# Sheet1.net
KiCad netlist of a schematic drawn in Altium Designer
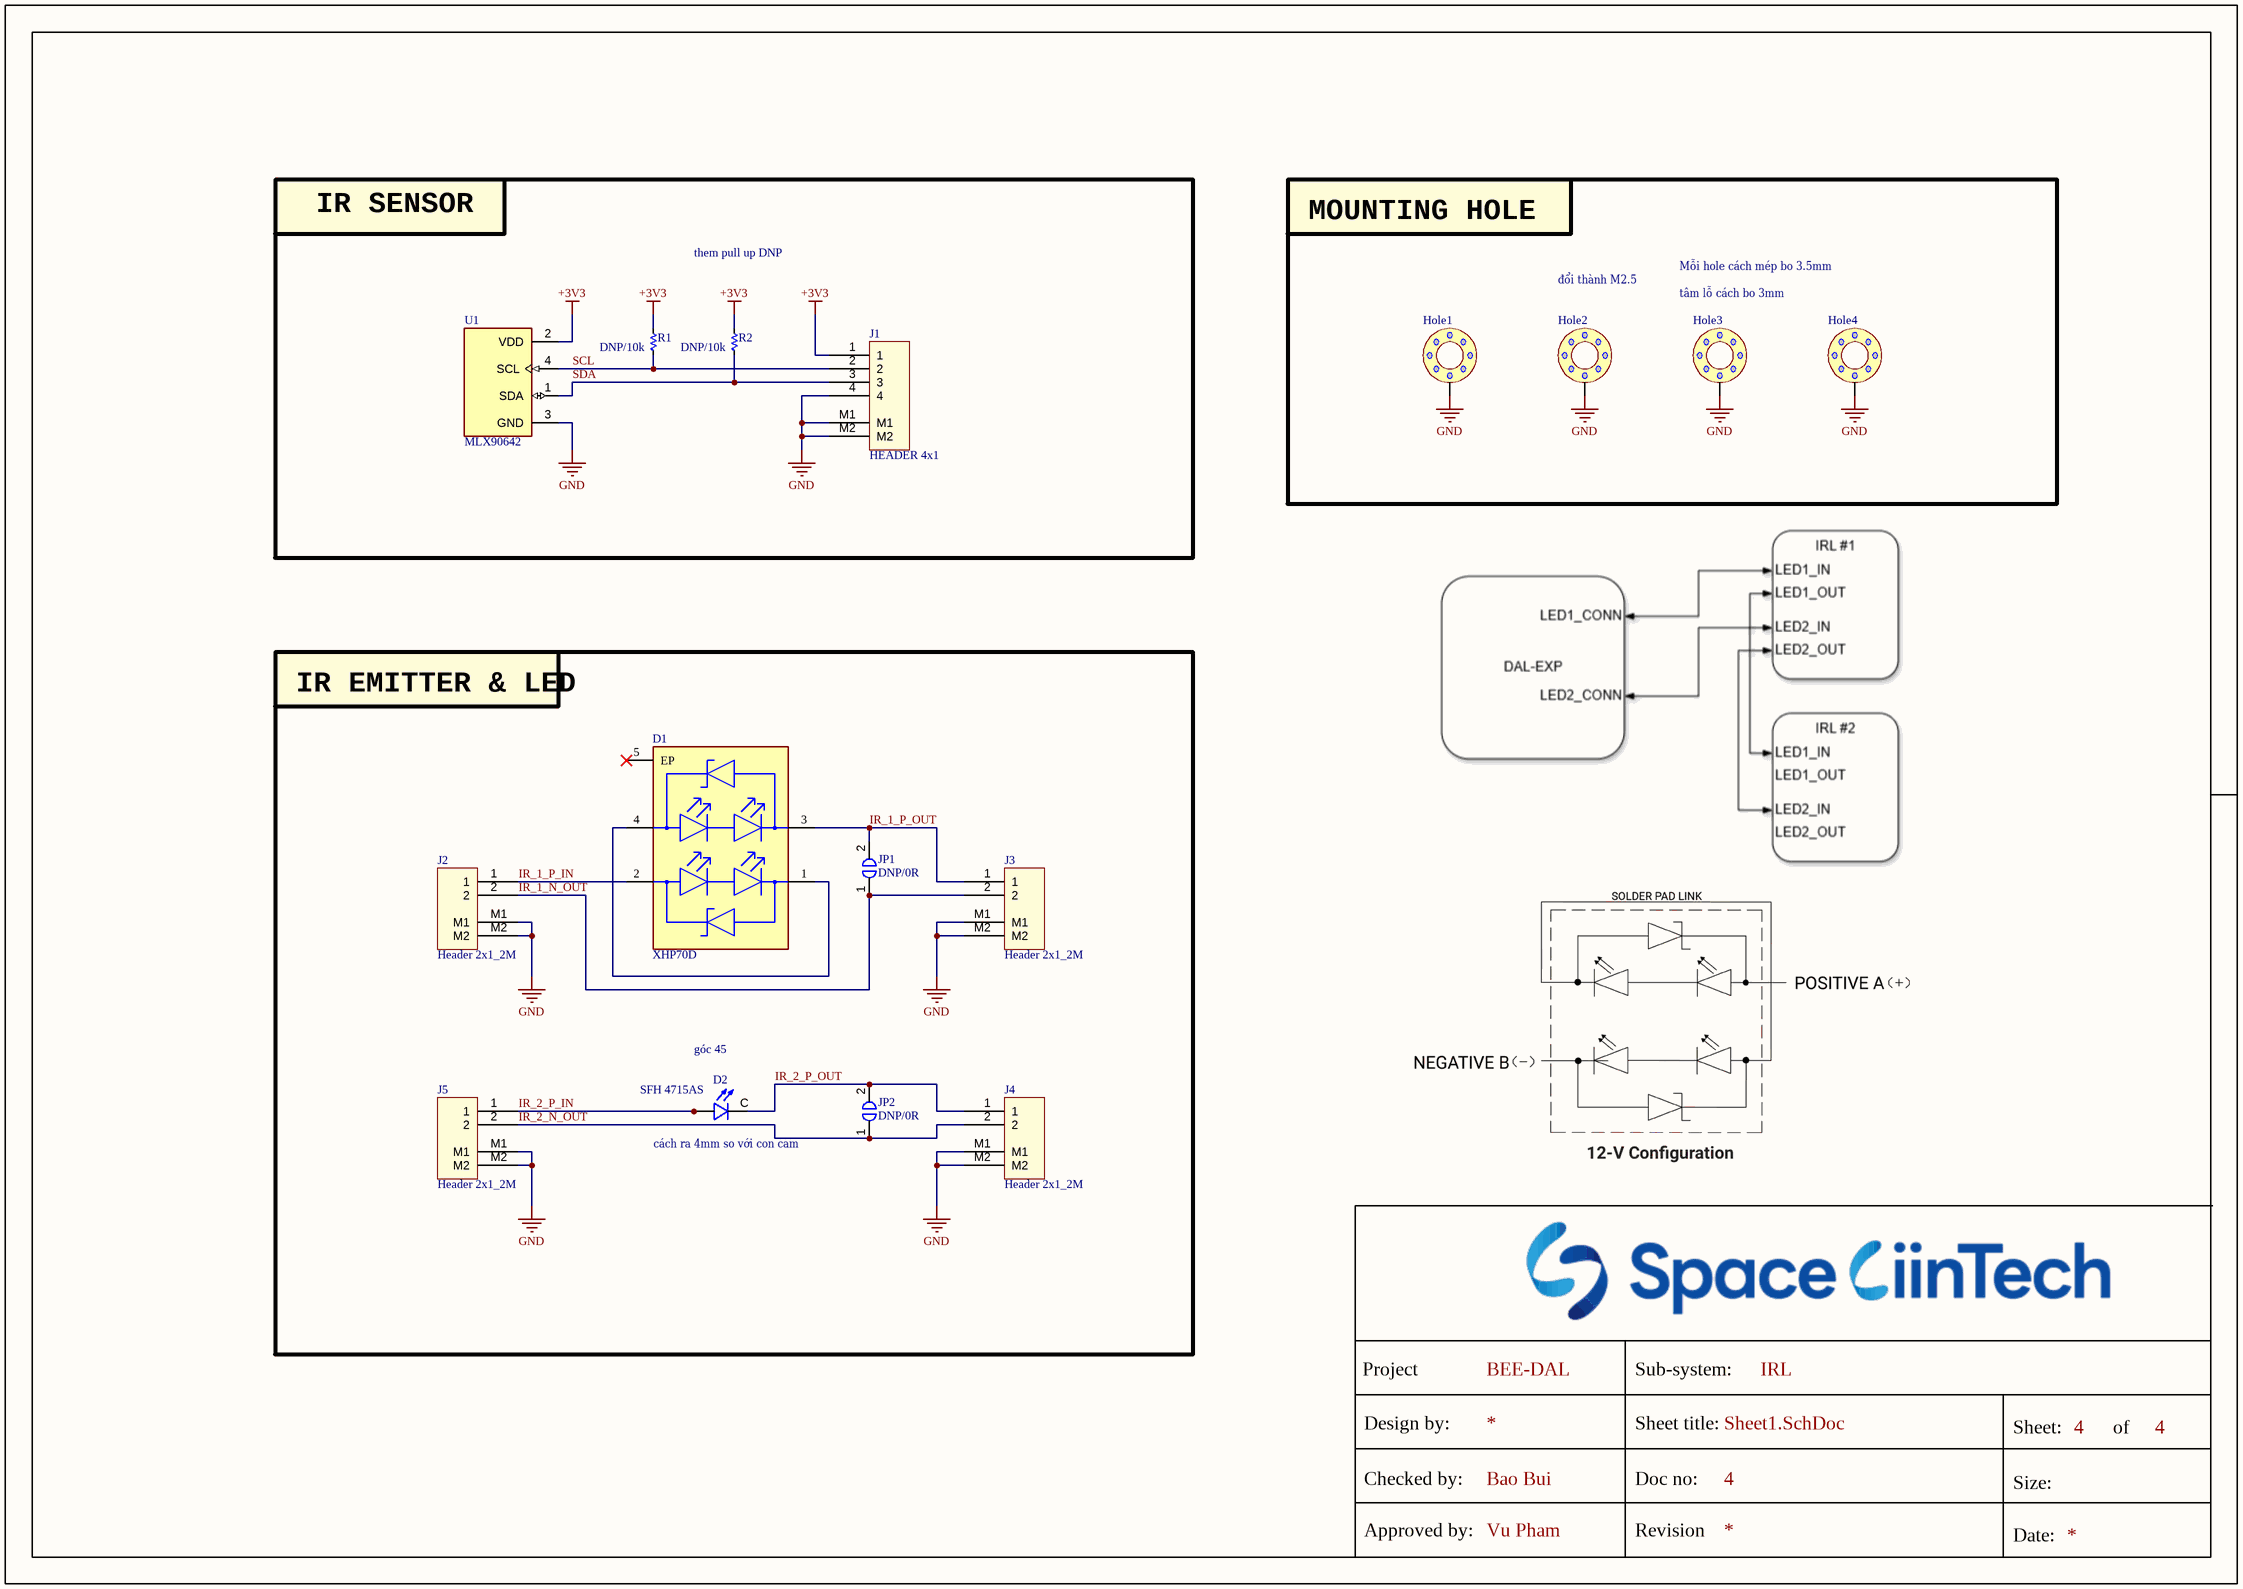
[diagram p0: Sheet1.SchDoc]

(export (version "E")
  (design (tool "Eeschema 10.0.6"))
  (components
    (comp (ref "D1")
      (value "XHP70D")
      (footprint "XHP70.3 High Intensity")
      (description "LED Lighting XLamp® XHP70.3 White, Cool 5000K 11.2V 1.05A 120° 2828")
      (libsource (lib "BEE_DAL_IRL") (part "XHP70D"))
    )
    (comp (ref "D2")
      (value "SFH 4715AS")
      (footprint "SFH 4715AS")
      (description "Infrared (IR) Emitter 860nm 3.2V 1.5A")
      (libsource (lib "BEE_DAL_IRL") (part "SFH 4715AS"))
    )
    (comp (ref "Hole1")
      (value "hole_space")
      (footprint "HEX-M3_NoVia")
      (libsource (lib "IFBschelib") (part "hole_space"))
    )
    (comp (ref "Hole2")
      (value "hole_space")
      (footprint "HEX-M3_NoVia")
      (libsource (lib "IFBschelib") (part "hole_space"))
    )
    (comp (ref "Hole3")
      (value "hole_space")
      (footprint "HEX-M3_NoVia")
      (libsource (lib "IFBschelib") (part "hole_space"))
    )
    (comp (ref "Hole4")
      (value "hole_space")
      (footprint "HEX-M3_NoVia")
      (libsource (lib "IFBschelib") (part "hole_space"))
    )
    (comp (ref "J1")
      (value "HEADER 4x1")
      (footprint "MOLEX_0532610471")
      (libsource (lib "LABLIB") (part "Header 4x1_2M"))
    )
    (comp (ref "J2")
      (value "Header 2x1_2M")
      (footprint "MOLEX_0532610271")
      (libsource (lib "") (part "Header 2x1_2M_1"))
    )
    (comp (ref "J3")
      (value "Header 2x1_2M")
      (footprint "MOLEX_0532610271")
      (libsource (lib "LABLIB") (part "Header 2x1_2M"))
    )
    (comp (ref "J4")
      (value "Header 2x1_2M")
      (footprint "MOLEX_0532610271")
      (libsource (lib "LABLIB") (part "Header 2x1_2M"))
    )
    (comp (ref "J5")
      (value "Header 2x1_2M")
      (footprint "MOLEX_0532610271")
      (libsource (lib "") (part "Header 2x1_2M_1"))
    )
    (comp (ref "JP1")
      (value "DNP/0R")
      (footprint "JUMPER_1608")
      (libsource (lib "LABLIB") (part "JUMPER_1_1"))
    )
    (comp (ref "JP2")
      (value "DNP/0R")
      (footprint "JUMPER_1608")
      (libsource (lib "LABLIB") (part "JUMPER_1_1"))
    )
    (comp (ref "R1")
      (value "DNP/10k")
      (footprint "RES_C_1608X60")
      (description "RES")
      (libsource (lib "IFBschelib") (part "_RES_B_2"))
    )
    (comp (ref "R2")
      (value "DNP/10k")
      (footprint "RES_C_1608X60")
      (description "RES")
      (libsource (lib "IFBschelib") (part "_RES_B_2"))
    )
    (comp (ref "U1")
      (value "MLX90642")
      (footprint "TO39 package")
      (description "32X24 THERMAL ARRAY, 110DEG FOV")
      (libsource (lib "BEE_DAL_IRL") (part "MLX90642"))
    )
  )
  (nets
    (net (code "1") (name "+3V3") (class "Default")
      (node (ref "J1") (pin "1") (pinfunction "1_1") (pintype "passive"))
      (node (ref "R1") (pin "1") (pinfunction "1_1") (pintype "passive"))
      (node (ref "R2") (pin "1") (pinfunction "1_1") (pintype "passive"))
      (node (ref "U1") (pin "2") (pinfunction "VDD_2") (pintype "power_in"))
    )
    (net (code "2") (name "/IR_1_N_OUT") (class "Default")
      (node (ref "J2") (pin "2") (pinfunction "2_2") (pintype "passive"))
      (node (ref "J3") (pin "2") (pinfunction "2_2") (pintype "passive"))
      (node (ref "JP1") (pin "1") (pinfunction "1_1") (pintype "passive"))
    )
    (net (code "3") (name "/IR_1_P_IN") (class "Default")
      (node (ref "D1") (pin "2") (pinfunction "1_ANODE_2") (pintype "passive"))
      (node (ref "J2") (pin "1") (pinfunction "1_1") (pintype "passive"))
    )
    (net (code "4") (name "/IR_1_P_OUT") (class "Default")
      (node (ref "D1") (pin "3") (pinfunction "2_CATHODE_3") (pintype "passive"))
      (node (ref "J3") (pin "1") (pinfunction "1_1") (pintype "passive"))
      (node (ref "JP1") (pin "2") (pinfunction "2_2") (pintype "passive"))
    )
    (net (code "5") (name "/IR_2_N_OUT") (class "Default")
      (node (ref "J4") (pin "2") (pinfunction "2_2") (pintype "passive"))
      (node (ref "J5") (pin "2") (pinfunction "2_2") (pintype "passive"))
      (node (ref "JP2") (pin "1") (pinfunction "1_1") (pintype "passive"))
    )
    (net (code "6") (name "/IR_2_P_IN") (class "Default")
      (node (ref "D2") (pin "A1") (pinfunction "A_A1") (pintype "passive"))
      (node (ref "D2") (pin "A2") (pinfunction "A_A2") (pintype "passive"))
      (node (ref "J5") (pin "1") (pinfunction "1_1") (pintype "passive"))
    )
    (net (code "7") (name "/IR_2_P_OUT") (class "Default")
      (node (ref "D2") (pin "C") (pinfunction "C_C") (pintype "passive"))
      (node (ref "J4") (pin "1") (pinfunction "1_1") (pintype "passive"))
      (node (ref "JP2") (pin "2") (pinfunction "2_2") (pintype "passive"))
    )
    (net (code "8") (name "/SCL") (class "Default")
      (node (ref "J1") (pin "2") (pinfunction "2_2") (pintype "passive"))
      (node (ref "R1") (pin "2") (pinfunction "2_2") (pintype "passive"))
      (node (ref "U1") (pin "4") (pinfunction "SCL_4") (pintype "input"))
    )
    (net (code "9") (name "/SDA") (class "Default")
      (node (ref "J1") (pin "3") (pinfunction "3_3") (pintype "passive"))
      (node (ref "R2") (pin "2") (pinfunction "2_2") (pintype "passive"))
      (node (ref "U1") (pin "1") (pinfunction "SDA_1") (pintype "bidirectional"))
    )
    (net (code "10") (name "GND") (class "Default")
      (node (ref "Hole1") (pin "1") (pinfunction "1_1") (pintype "passive"))
      (node (ref "Hole2") (pin "1") (pinfunction "1_1") (pintype "passive"))
      (node (ref "Hole3") (pin "1") (pinfunction "1_1") (pintype "passive"))
      (node (ref "Hole4") (pin "1") (pinfunction "1_1") (pintype "passive"))
      (node (ref "J1") (pin "4") (pinfunction "4_4") (pintype "passive"))
      (node (ref "J1") (pin "M1") (pinfunction "M1_M1") (pintype "passive"))
      (node (ref "J1") (pin "M2") (pinfunction "M2_M2") (pintype "passive"))
      (node (ref "J2") (pin "M1") (pinfunction "M1_M1") (pintype "passive"))
      (node (ref "J2") (pin "M2") (pinfunction "M2_M2") (pintype "passive"))
      (node (ref "J3") (pin "M1") (pinfunction "M1_M1") (pintype "passive"))
      (node (ref "J3") (pin "M2") (pinfunction "M2_M2") (pintype "passive"))
      (node (ref "J4") (pin "M1") (pinfunction "M1_M1") (pintype "passive"))
      (node (ref "J4") (pin "M2") (pinfunction "M2_M2") (pintype "passive"))
      (node (ref "J5") (pin "M1") (pinfunction "M1_M1") (pintype "passive"))
      (node (ref "J5") (pin "M2") (pinfunction "M2_M2") (pintype "passive"))
      (node (ref "U1") (pin "3") (pinfunction "GND_3") (pintype "power_in"))
    )
    (net (code "11") (name "Net-(D1-1_CATHODE)") (class "Default")
      (node (ref "D1") (pin "1") (pinfunction "1_CATHODE_1") (pintype "passive"))
      (node (ref "D1") (pin "4") (pinfunction "2_ANODE_4") (pintype "passive"))
    )
    (net (code "12") (name "unconnected-(D1-EP-Pad5)") (class "Default")
      (node (ref "D1") (pin "5") (pinfunction "EP_5") (pintype "passive+no_connect"))
    )
  )
)
